# Regelaar.net
KiCad netlist of a schematic drawn in Altium Designer
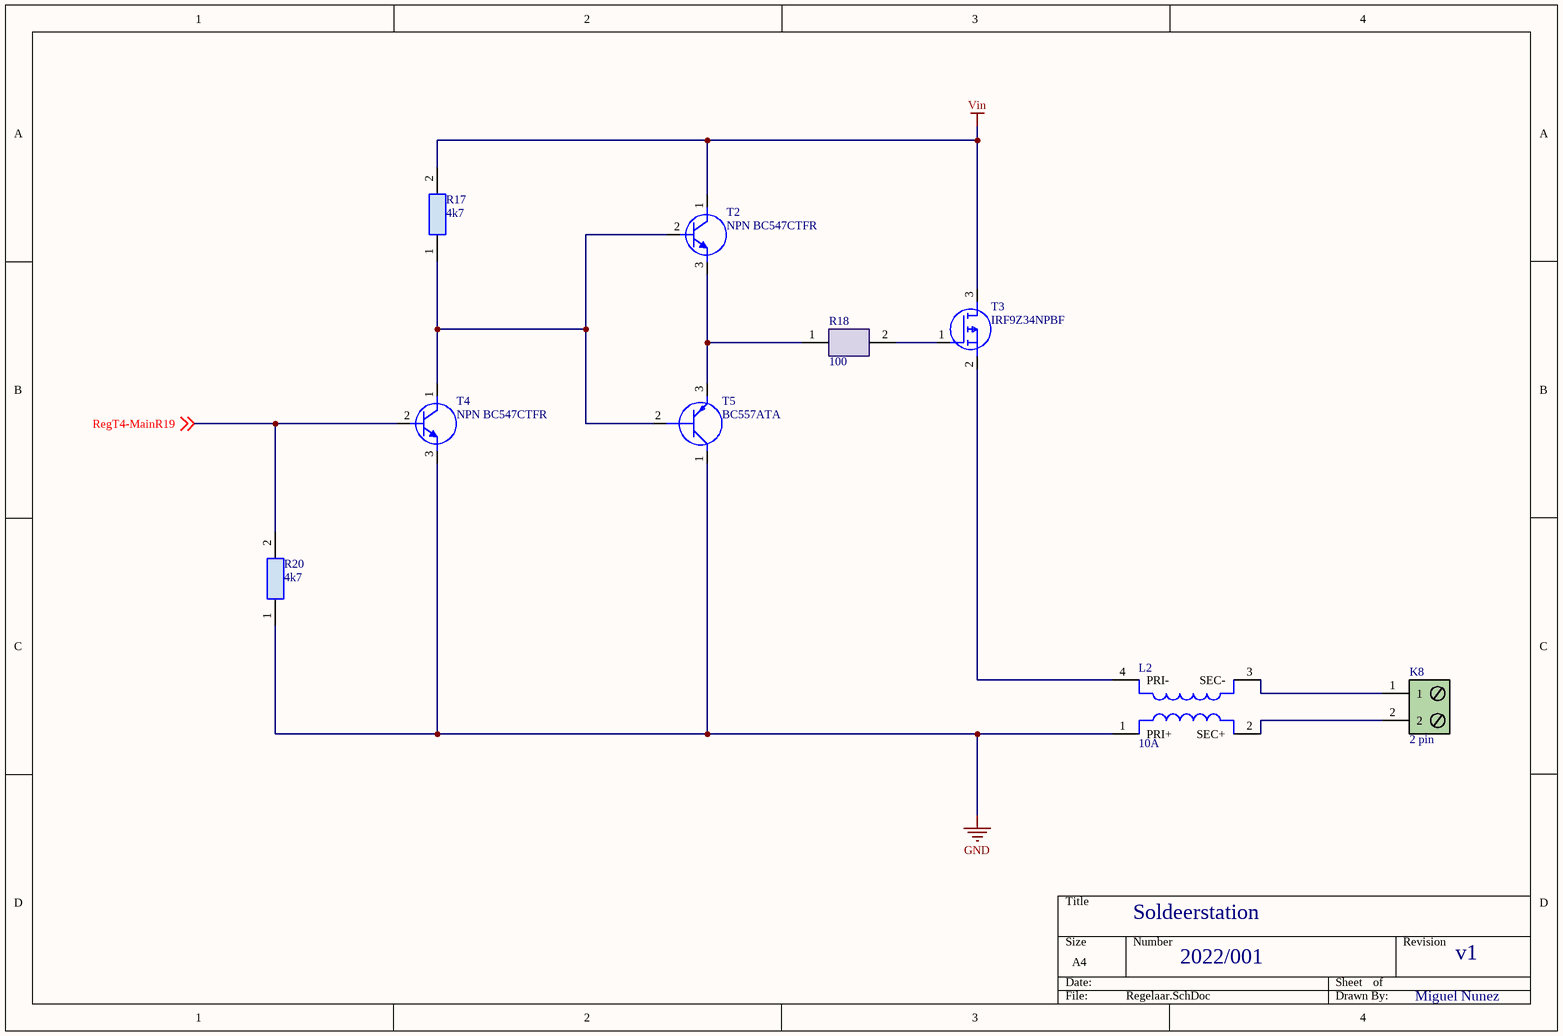
[diagram p0: Regelaar.SchDoc]

(export (version "E")
  (design (tool "Eeschema 10.0.6"))
  (components
    (comp (ref "K8")
      (value "2 pin")
      (footprint "SamacSys:1729128")
      (description "Connector Term. blok. 1729128 2 pin")
      (fields (field (name "MANUFACTURER_PART_NUMBER") "1729128"))
      (libsource (lib "PO_SS_Lib") (part "Term. blok 2 pin"))
    )
    (comp (ref "L2")
      (value "10A")
      (footprint "SamacSys:CM2545X171B10")
      (description "common mode smoorspoel 10A")
      (fields (field (name "MANUFACTURER_PART_NUMBER") "CM2545X171B-10"))
      (libsource (lib "PO_SS_Lib") (part "CM2545X171B-10"))
    )
    (comp (ref "R17")
      (value "4k7")
      (footprint "SamacSys:CAPC2012X65N")
      (description "4k7 SMD 0805  ESR10EZPJ472")
      (fields (field (name "MANUFACTURER_PART_NUMBER") "ESR10EZPJ472"))
      (libsource (lib "PO_SS_Lib") (part "RES 4k7 0805"))
    )
    (comp (ref "R18")
      (value "100")
      (footprint "SamacSys:RESC1220X65N")
      (description "100 Ohm SMD 0508  LTR10EZPJ101")
      (fields
        (field (name "MOUSER2 PART NUMBER") "755-LTR10EZPJ101")
        (field (name "MANUFACTURER_PART_NUMBER") "LTR10EZPJ101")
      )
      (libsource (lib "PO_SS_Lib") (part "RES 100 0508"))
    )
    (comp (ref "R20")
      (value "4k7")
      (footprint "SamacSys:CAPC2012X65N")
      (description "4k7 SMD 0805  ESR10EZPJ472")
      (fields (field (name "MANUFACTURER_PART_NUMBER") "ESR10EZPJ472"))
      (libsource (lib "PO_SS_Lib") (part "RES 4k7 0805"))
    )
    (comp (ref "T2")
      (value "NPN BC547CTFR")
      (footprint "BC33740TA")
      (description "Transistor BC547CTFR NPN")
      (fields
        (field (name "MANUFACTURER_PART_NUMBER") "BC547CTFR")
        (field (name "COPYRIGHT") "Copyright (C) 2022 Ultra Librarian. All rights reserved.")
      )
      (libsource (lib "PO_SS_Lib") (part "TR BC547CTFR"))
    )
    (comp (ref "T3")
      (value "IRF9Z34NPBF")
      (footprint "SamacSys:TO254P469X1042X1967-3P")
      (description "MOSFET (P-Channel)")
      (fields (field (name "MOUSER2 PART NUMBER") "942-IRF9Z34NPBF"))
      (libsource (lib "PO_SS_Lib") (part "TR IRF9Z34NPBF"))
    )
    (comp (ref "T4")
      (value "NPN BC547CTFR")
      (footprint "BC33740TA")
      (description "Transistor BC547CTFR NPN")
      (fields
        (field (name "MANUFACTURER_PART_NUMBER") "BC547CTFR")
        (field (name "COPYRIGHT") "Copyright (C) 2022 Ultra Librarian. All rights reserved.")
      )
      (libsource (lib "PO_SS_Lib") (part "TR BC547CTFR"))
    )
    (comp (ref "T5")
      (value "BC557ATA")
      (footprint "SamacSys:BC33740TA")
      (description "Transistor BJT BC557ATA PNP")
      (fields (field (name "MOUSER2 PART NUMBER") "512-BC557ATA"))
      (libsource (lib "PO_SS_Lib") (part "TR BC557ATA"))
    )
  )
  (nets
    (net (code "1") (name "GND") (class "Default")
      (node (ref "L2") (pin "1") (pinfunction "PRI+_1") (pintype "passive"))
      (node (ref "R20") (pin "1") (pinfunction "1_1") (pintype "passive"))
      (node (ref "T4") (pin "3") (pinfunction "E_3") (pintype "passive"))
      (node (ref "T5") (pin "1") (pinfunction "C_1") (pintype "passive"))
    )
    (net (code "2") (name "Net-(L2-PRI-)") (class "Default")
      (node (ref "L2") (pin "4") (pinfunction "PRI-_4") (pintype "passive"))
      (node (ref "T3") (pin "2") (pinfunction "S_2") (pintype "passive"))
    )
    (net (code "3") (name "Net-(L2-SEC+)") (class "Default")
      (node (ref "K8") (pin "2") (pinfunction "2_2") (pintype "passive"))
      (node (ref "L2") (pin "2") (pinfunction "SEC+_2") (pintype "passive"))
    )
    (net (code "4") (name "Net-(L2-SEC-)") (class "Default")
      (node (ref "K8") (pin "1") (pinfunction "1_1") (pintype "passive"))
      (node (ref "L2") (pin "3") (pinfunction "SEC-_3") (pintype "passive"))
    )
    (net (code "5") (name "Net-(T2-B)") (class "Default")
      (node (ref "R17") (pin "1") (pinfunction "1_1") (pintype "passive"))
      (node (ref "T2") (pin "2") (pinfunction "B_2") (pintype "passive"))
      (node (ref "T4") (pin "1") (pinfunction "C_1") (pintype "passive"))
      (node (ref "T5") (pin "2") (pinfunction "B_2") (pintype "passive"))
    )
    (net (code "6") (name "Net-(T2-E)") (class "Default")
      (node (ref "R18") (pin "1") (pinfunction "1_1") (pintype "passive"))
      (node (ref "T2") (pin "3") (pinfunction "E_3") (pintype "passive"))
      (node (ref "T5") (pin "3") (pinfunction "E_3") (pintype "passive"))
    )
    (net (code "7") (name "Net-(T3-G)") (class "Default")
      (node (ref "R18") (pin "2") (pinfunction "2_2") (pintype "passive"))
      (node (ref "T3") (pin "1") (pinfunction "G_1") (pintype "passive"))
    )
    (net (code "8") (name "RegT4-MainR19") (class "Default")
      (node (ref "R20") (pin "2") (pinfunction "2_2") (pintype "passive"))
      (node (ref "T4") (pin "2") (pinfunction "B_2") (pintype "passive"))
    )
    (net (code "9") (name "Vin") (class "Default")
      (node (ref "R17") (pin "2") (pinfunction "2_2") (pintype "passive"))
      (node (ref "T2") (pin "1") (pinfunction "C_1") (pintype "passive"))
      (node (ref "T3") (pin "3") (pinfunction "D_3") (pintype "passive"))
    )
  )
)
